# mSniff_v01.net
KiCad netlist of a schematic drawn in EAGLE
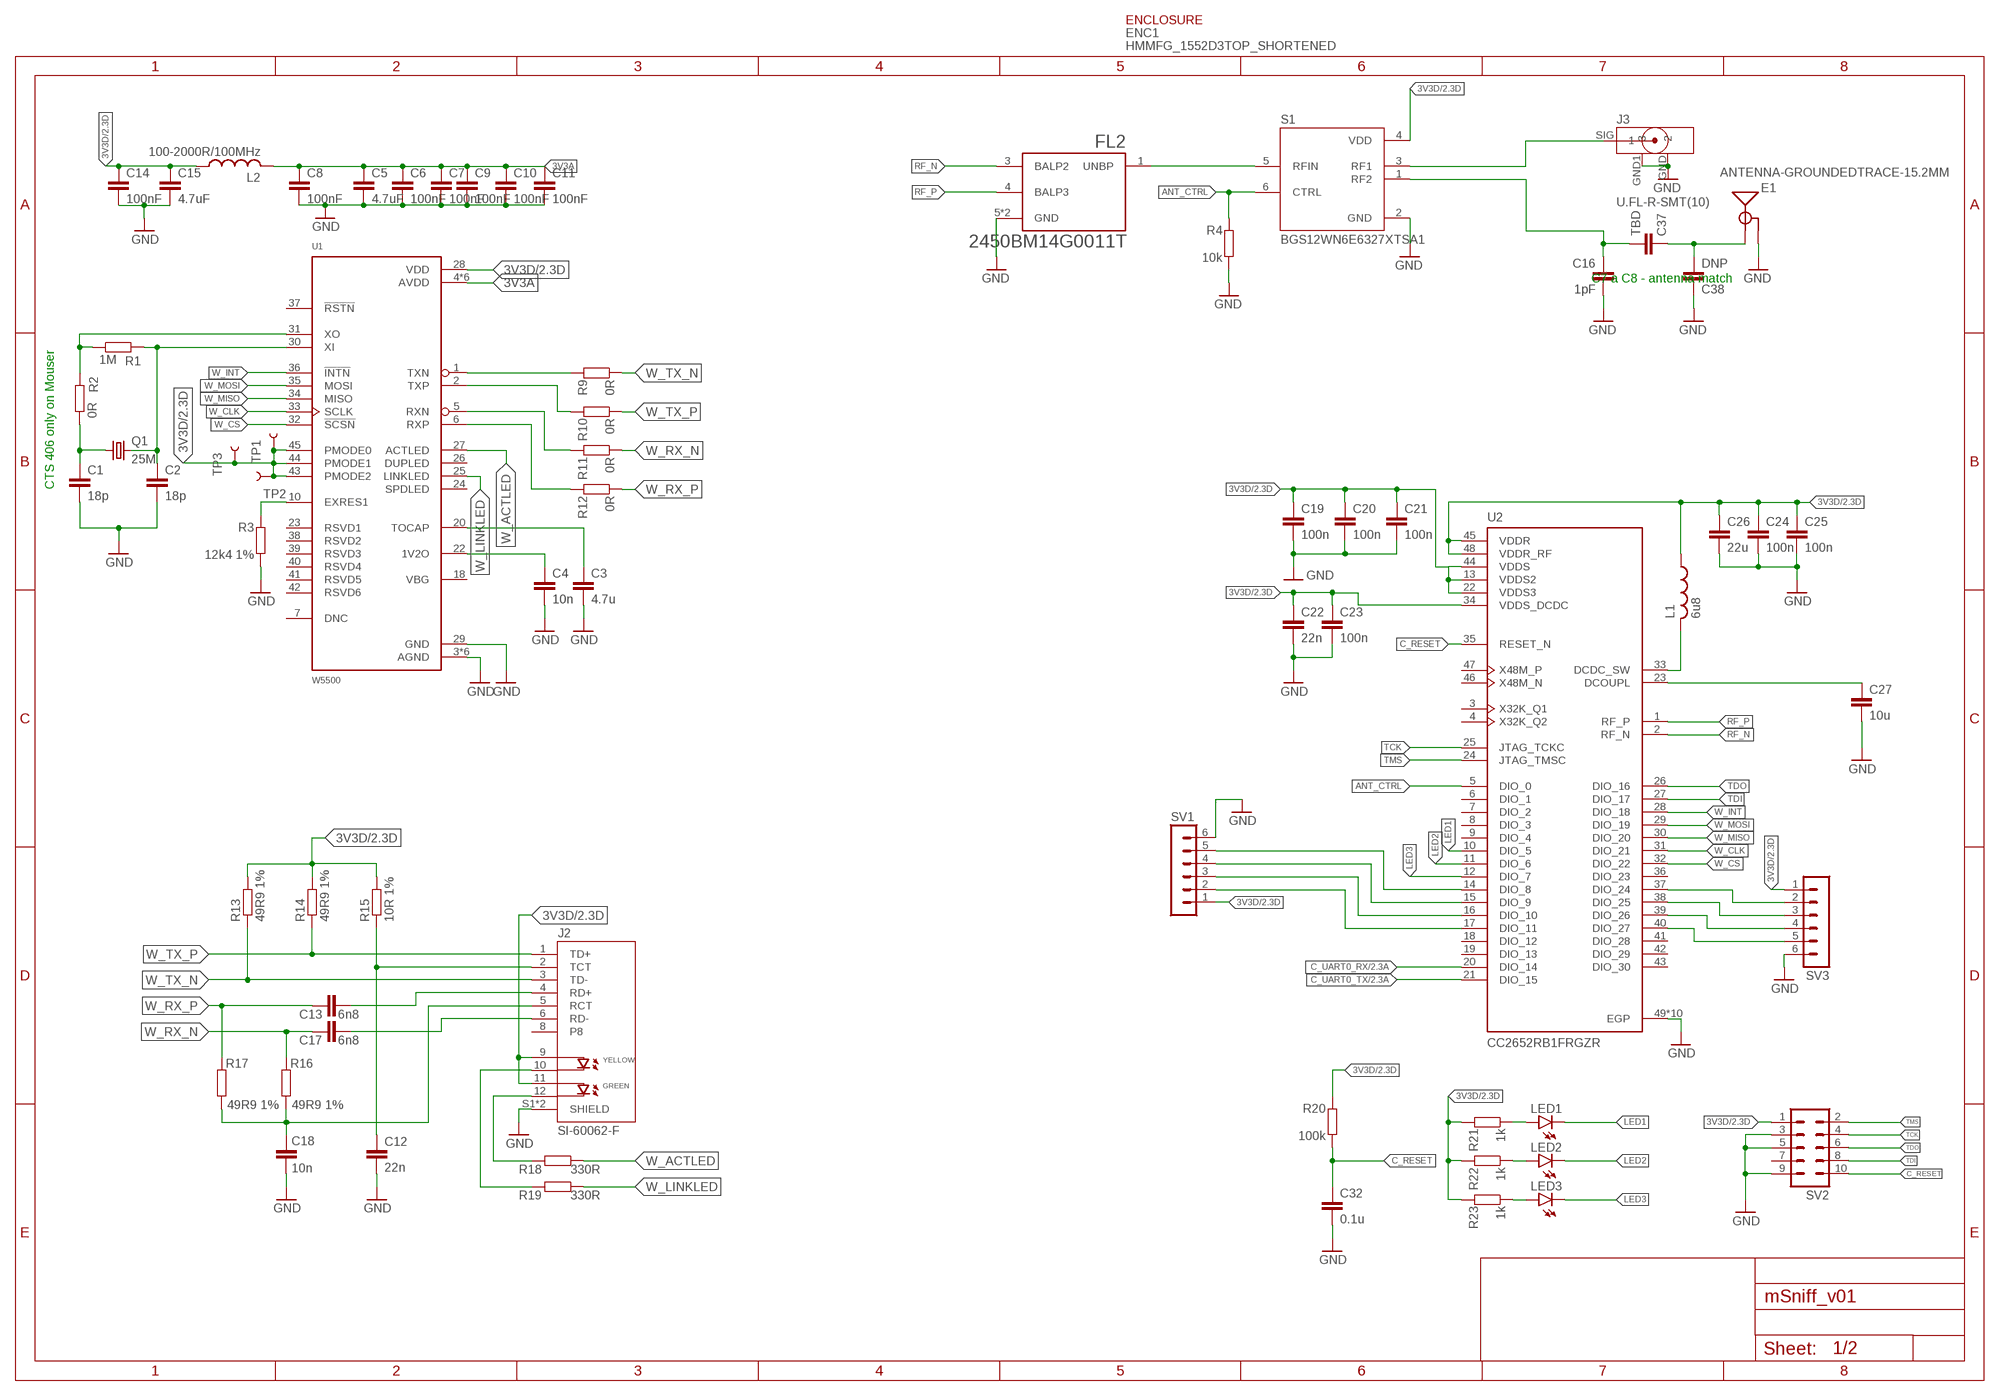
[diagram p0: schematic, sheet 1]
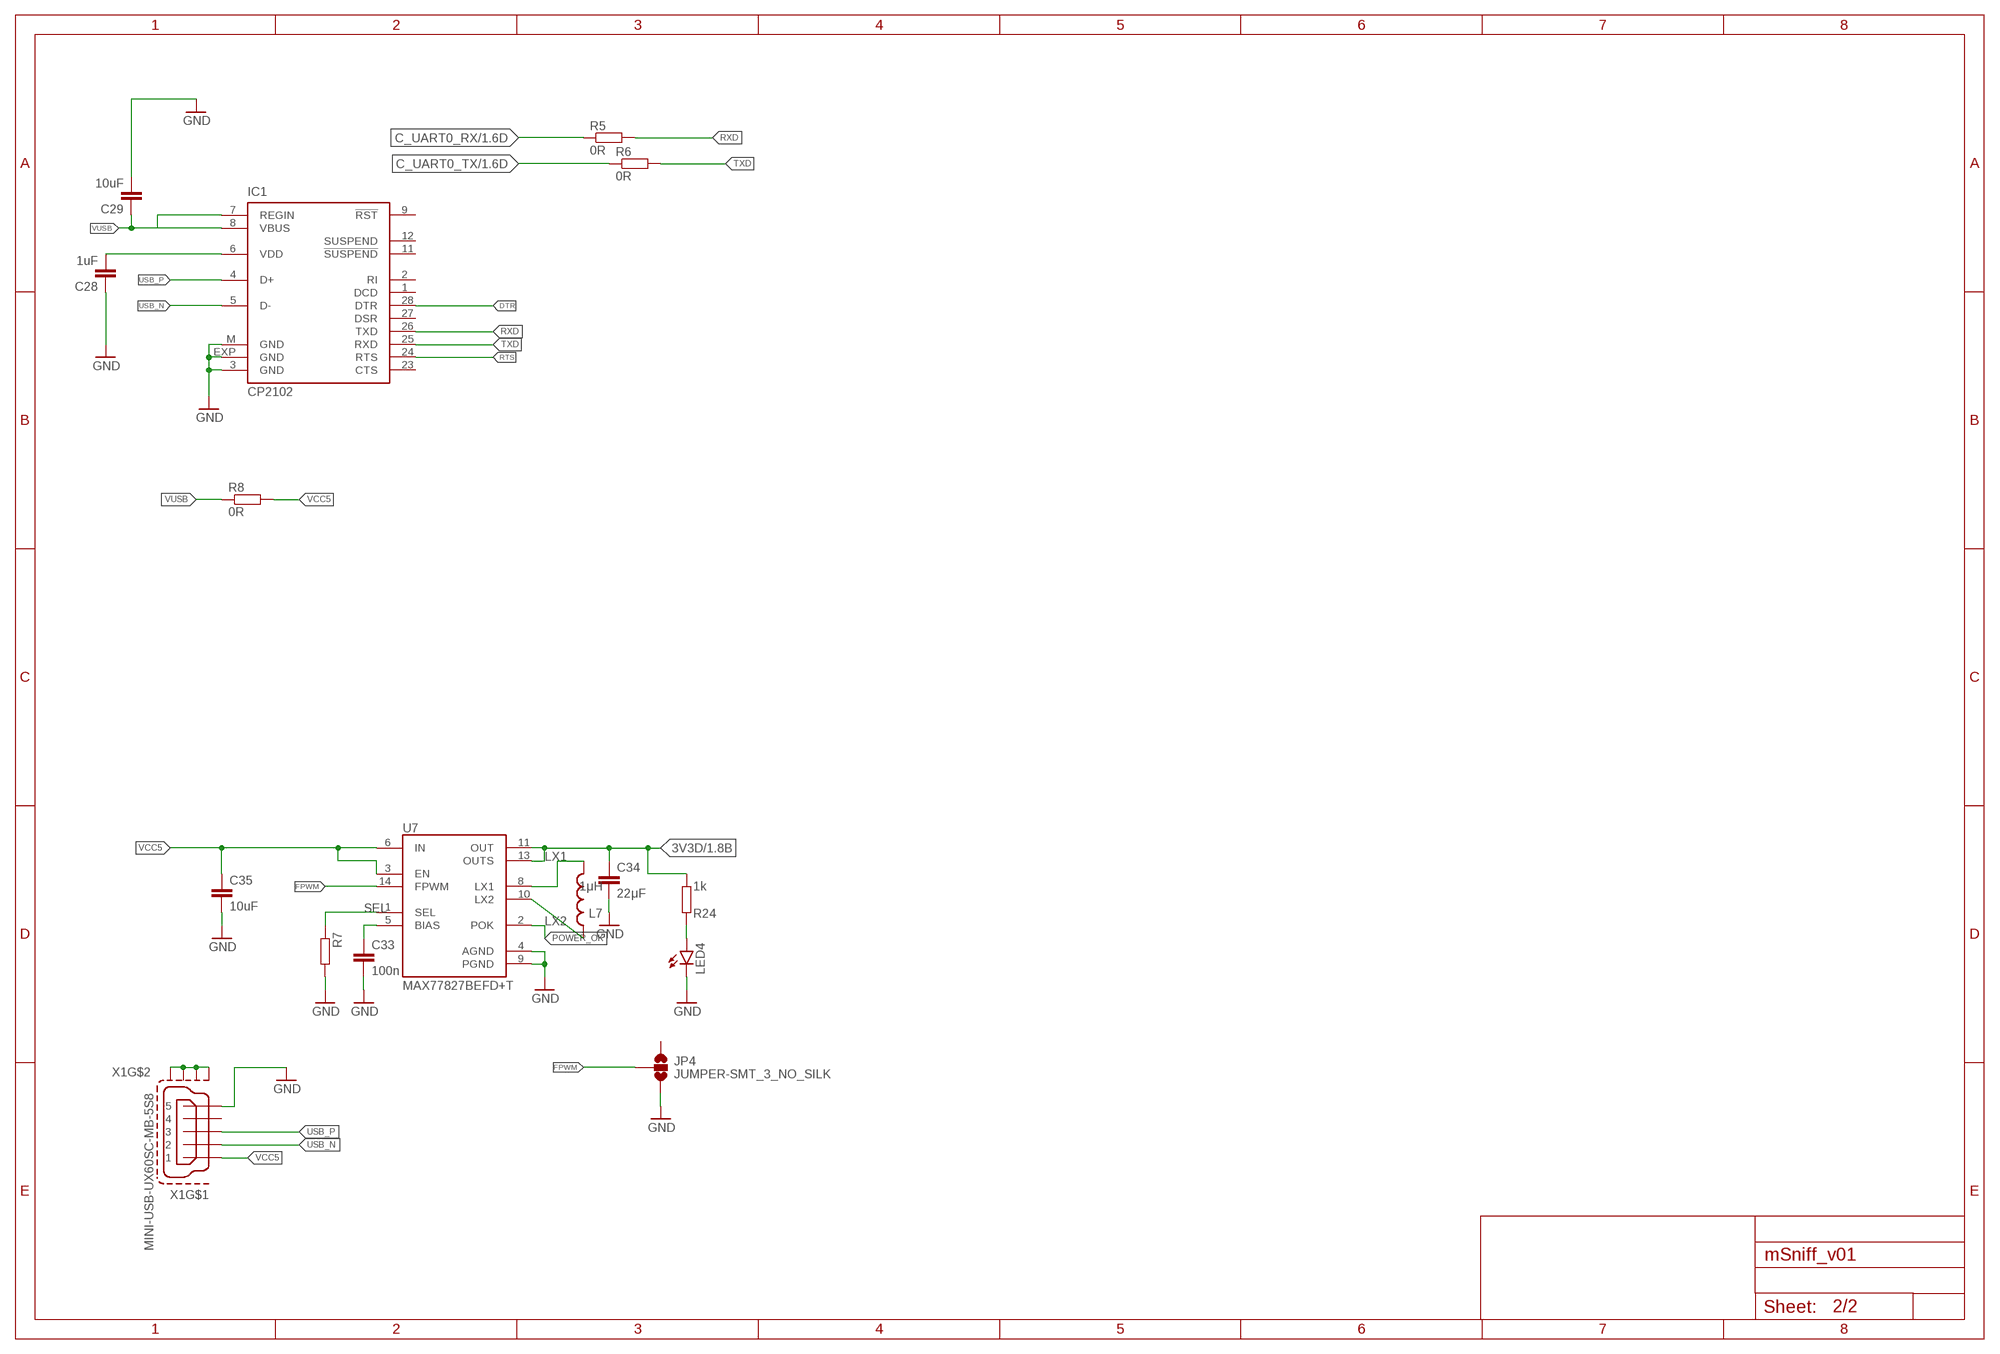
[diagram p1: schematic, sheet 2]

(export (version "E")
  (design (tool "Eeschema 10.0.6"))
  (components
    (comp (ref "C1")
      (value "18p")
      (footprint "eagle-import:0603REC_C")
      (libsource (lib "eagle-import") (part "C_0603REC"))
    )
    (comp (ref "C2")
      (value "18p")
      (footprint "eagle-import:0603REC_C")
      (libsource (lib "eagle-import") (part "C_0603REC"))
    )
    (comp (ref "C3")
      (value "4.7u")
      (footprint "eagle-import:0603REC_C")
      (libsource (lib "eagle-import") (part "C_0603REC"))
    )
    (comp (ref "C4")
      (value "10n")
      (footprint "eagle-import:0603REC_C")
      (libsource (lib "eagle-import") (part "C_0603REC"))
    )
    (comp (ref "C5")
      (value "4.7uF")
      (footprint "eagle-import:0805REC_C")
      (libsource (lib "eagle-import") (part "C_0805REC"))
    )
    (comp (ref "C6")
      (value "100nF")
      (footprint "eagle-import:0603REC_C")
      (libsource (lib "eagle-import") (part "C_0603REC"))
    )
    (comp (ref "C7")
      (value "100nF")
      (footprint "eagle-import:0603REC_C")
      (libsource (lib "eagle-import") (part "C_0603REC"))
    )
    (comp (ref "C8")
      (value "100nF")
      (footprint "eagle-import:0603REC_C")
      (libsource (lib "eagle-import") (part "C_0603REC"))
    )
    (comp (ref "C9")
      (value "100nF")
      (footprint "eagle-import:0603REC_C")
      (libsource (lib "eagle-import") (part "C_0603REC"))
    )
    (comp (ref "C10")
      (value "100nF")
      (footprint "eagle-import:0603REC_C")
      (libsource (lib "eagle-import") (part "C_0603REC"))
    )
    (comp (ref "C11")
      (value "100nF")
      (footprint "eagle-import:0603REC_C")
      (libsource (lib "eagle-import") (part "C_0603REC"))
    )
    (comp (ref "C12")
      (value "22n")
      (footprint "eagle-import:0603REC_C")
      (libsource (lib "eagle-import") (part "C_0603REC"))
    )
    (comp (ref "C13")
      (value "6n8")
      (footprint "eagle-import:0603REC_C")
      (libsource (lib "eagle-import") (part "C_0603REC"))
    )
    (comp (ref "C14")
      (value "100nF")
      (footprint "eagle-import:0603REC_C")
      (libsource (lib "eagle-import") (part "C_0603REC"))
    )
    (comp (ref "C15")
      (value "4.7uF")
      (footprint "eagle-import:0805REC_C")
      (libsource (lib "eagle-import") (part "C_0805REC"))
    )
    (comp (ref "C16")
      (value "1pF")
      (footprint "eagle-import:0402REC_C")
      (libsource (lib "eagle-import") (part "C_0402REC"))
    )
    (comp (ref "C17")
      (value "6n8")
      (footprint "eagle-import:0603REC_C")
      (libsource (lib "eagle-import") (part "C_0603REC"))
    )
    (comp (ref "C18")
      (value "10n")
      (footprint "eagle-import:0603REC_C")
      (libsource (lib "eagle-import") (part "C_0603REC"))
    )
    (comp (ref "C19")
      (value "100n")
      (footprint "eagle-import:0603REC_C")
      (libsource (lib "eagle-import") (part "C_0603REC"))
    )
    (comp (ref "C20")
      (value "100n")
      (footprint "eagle-import:0603REC_C")
      (libsource (lib "eagle-import") (part "C_0603REC"))
    )
    (comp (ref "C21")
      (value "100n")
      (footprint "eagle-import:0603REC_C")
      (libsource (lib "eagle-import") (part "C_0603REC"))
    )
    (comp (ref "C22")
      (value "22n")
      (footprint "eagle-import:0603REC_C")
      (libsource (lib "eagle-import") (part "C_0603REC"))
    )
    (comp (ref "C23")
      (value "100n")
      (footprint "eagle-import:0603REC_C")
      (libsource (lib "eagle-import") (part "C_0603REC"))
    )
    (comp (ref "C24")
      (value "100n")
      (footprint "eagle-import:0603REC_C")
      (libsource (lib "eagle-import") (part "C_0603REC"))
    )
    (comp (ref "C25")
      (value "100n")
      (footprint "eagle-import:0603REC_C")
      (libsource (lib "eagle-import") (part "C_0603REC"))
    )
    (comp (ref "C26")
      (value "22u")
      (footprint "eagle-import:0603REC_C")
      (libsource (lib "eagle-import") (part "C_0603REC"))
    )
    (comp (ref "C27")
      (value "10u")
      (footprint "eagle-import:0603REC_C")
      (libsource (lib "eagle-import") (part "C_0603REC"))
    )
    (comp (ref "C32")
      (value "0.1u")
      (footprint "eagle-import:0603REC_C")
      (libsource (lib "eagle-import") (part "C_0603REC"))
    )
    (comp (ref "C37")
      (value "TBD")
      (footprint "eagle-import:0402REC_C")
      (libsource (lib "eagle-import") (part "C_0402REC"))
    )
    (comp (ref "C38")
      (value "DNP")
      (footprint "eagle-import:0402REC_C")
      (libsource (lib "eagle-import") (part "C_0402REC"))
    )
    (comp (ref "E1")
      (value "ANTENNA-GROUNDEDTRACE-15.2MM")
      (footprint "eagle-import:TRACE_ANTENNA_2.4GHZ_15.2MM")
      (libsource (lib "eagle-import") (part "ANTENNA-GROUNDEDTRACE-15.2MM"))
    )
    (comp (ref "ENC1")
      (value "HMMFG_1552D3TOP_SHORTENED")
      (footprint "eagle-import:1552D3_TOP_SHORT")
      (libsource (lib "eagle-import") (part "HMMFG_1552D3TOP_SHORTENED"))
    )
    (comp (ref "FL2")
      (value "2450BM14G0011T")
      (footprint "eagle-import:BALUN_2450BM14G0011T")
      (fields (field (name "MF") "Johanson Technology"))
      (libsource (lib "eagle-import") (part "2450BM14G0011T"))
    )
    (comp (ref "J2")
      (value "SI-60062-F")
      (footprint "eagle-import:BEL_SI-60062-F")
      (fields (field (name "MF") "Bel Magnetic Solutions"))
      (libsource (lib "eagle-import") (part "SI-60062-F"))
    )
    (comp (ref "J3")
      (value "U.FL-R-SMT(10)")
      (footprint "eagle-import:U.FL-R-SMT(10)")
      (fields
        (field (name "DIGIKEY_PART_NUMBER") "H9161CT-ND")
        (field (name "MANUFACTURER") "Hirose Electric Co Ltd")
        (field (name "CREATED_BY") "PCBLayout.com")
      )
      (libsource (lib "eagle-import") (part "U.FL-R-SMT(10)"))
    )
    (comp (ref "L1")
      (value "6u8")
      (footprint "eagle-import:0805REC_L")
      (libsource (lib "eagle-import") (part "L_0805REC"))
    )
    (comp (ref "L2")
      (value "100-2000R/100MHz")
      (footprint "eagle-import:0603REC_L")
      (libsource (lib "eagle-import") (part "L_0603REC"))
    )
    (comp (ref "LED1")
      (value "LEDCHIPLED_0603")
      (footprint "eagle-import:CHIPLED_0603")
      (libsource (lib "eagle-import") (part "LEDCHIPLED_0603"))
    )
    (comp (ref "LED2")
      (value "LEDCHIPLED_0603")
      (footprint "eagle-import:CHIPLED_0603")
      (libsource (lib "eagle-import") (part "LEDCHIPLED_0603"))
    )
    (comp (ref "LED3")
      (value "LEDCHIPLED_0603")
      (footprint "eagle-import:CHIPLED_0603")
      (libsource (lib "eagle-import") (part "LEDCHIPLED_0603"))
    )
    (comp (ref "Q1")
      (value "25M")
      (footprint "eagle-import:CTS406")
      (libsource (lib "eagle-import") (part "CRYSTALCTS406"))
    )
    (comp (ref "R1")
      (value "1M")
      (footprint "eagle-import:0603REC_R")
      (libsource (lib "eagle-import") (part "R_0603REC"))
    )
    (comp (ref "R2")
      (value "0R")
      (footprint "eagle-import:0603REC_R")
      (libsource (lib "eagle-import") (part "R_0603REC"))
    )
    (comp (ref "R3")
      (value "12k4 1%")
      (footprint "eagle-import:0603REC_R")
      (libsource (lib "eagle-import") (part "R_0603REC"))
    )
    (comp (ref "R4")
      (value "10k")
      (footprint "eagle-import:0603REC_R")
      (libsource (lib "eagle-import") (part "R_0603REC"))
    )
    (comp (ref "R9")
      (value "0R")
      (footprint "eagle-import:0603REC_R")
      (libsource (lib "eagle-import") (part "R_0603REC"))
    )
    (comp (ref "R10")
      (value "0R")
      (footprint "eagle-import:0603REC_R")
      (libsource (lib "eagle-import") (part "R_0603REC"))
    )
    (comp (ref "R11")
      (value "0R")
      (footprint "eagle-import:0603REC_R")
      (libsource (lib "eagle-import") (part "R_0603REC"))
    )
    (comp (ref "R12")
      (value "0R")
      (footprint "eagle-import:0603REC_R")
      (libsource (lib "eagle-import") (part "R_0603REC"))
    )
    (comp (ref "R13")
      (value "49R9 1%")
      (footprint "eagle-import:0603REC_R")
      (libsource (lib "eagle-import") (part "R_0603REC"))
    )
    (comp (ref "R14")
      (value "49R9 1%")
      (footprint "eagle-import:0603REC_R")
      (libsource (lib "eagle-import") (part "R_0603REC"))
    )
    (comp (ref "R15")
      (value "10R 1%")
      (footprint "eagle-import:0603REC_R")
      (libsource (lib "eagle-import") (part "R_0603REC"))
    )
    (comp (ref "R16")
      (value "49R9 1%")
      (footprint "eagle-import:0603REC_R")
      (libsource (lib "eagle-import") (part "R_0603REC"))
    )
    (comp (ref "R17")
      (value "49R9 1%")
      (footprint "eagle-import:0603REC_R")
      (libsource (lib "eagle-import") (part "R_0603REC"))
    )
    (comp (ref "R18")
      (value "330R")
      (footprint "eagle-import:0603REC_R")
      (libsource (lib "eagle-import") (part "R_0603REC"))
    )
    (comp (ref "R19")
      (value "330R")
      (footprint "eagle-import:0603REC_R")
      (libsource (lib "eagle-import") (part "R_0603REC"))
    )
    (comp (ref "R20")
      (value "100k")
      (footprint "eagle-import:0603REC_R")
      (libsource (lib "eagle-import") (part "R_0603REC"))
    )
    (comp (ref "R21")
      (value "1k")
      (footprint "eagle-import:0603REC_R")
      (libsource (lib "eagle-import") (part "R_0603REC"))
    )
    (comp (ref "R22")
      (value "1k")
      (footprint "eagle-import:0603REC_R")
      (libsource (lib "eagle-import") (part "R_0603REC"))
    )
    (comp (ref "R23")
      (value "1k")
      (footprint "eagle-import:0603REC_R")
      (libsource (lib "eagle-import") (part "R_0603REC"))
    )
    (comp (ref "S1")
      (value "BGS12WN6E6327XTSA1")
      (footprint "eagle-import:SW_BGS12WN6E6327XTSA1")
      (fields (field (name "MF") "Infineon Technologies"))
      (libsource (lib "eagle-import") (part "BGS12WN6E6327XTSA1"))
    )
    (comp (ref "SV1")
      (value "MA06-1")
      (footprint "eagle-import:MA06-1")
      (libsource (lib "eagle-import") (part "MA06-1"))
    )
    (comp (ref "SV2")
      (value "MA05-2SMD127")
      (footprint "eagle-import:MA05-2-SMD127-GPEC214")
      (libsource (lib "eagle-import") (part "MA05-2SMD127"))
    )
    (comp (ref "SV3")
      (value "MA06-1")
      (footprint "eagle-import:MA06-1")
      (libsource (lib "eagle-import") (part "MA06-1"))
    )
    (comp (ref "TP1")
      (value "TEST-POINT3")
      (footprint "eagle-import:PAD.03X.03")
      (libsource (lib "eagle-import") (part "TEST-POINT3"))
    )
    (comp (ref "TP2")
      (value "TEST-POINT3")
      (footprint "eagle-import:PAD.03X.03")
      (libsource (lib "eagle-import") (part "TEST-POINT3"))
    )
    (comp (ref "TP3")
      (value "TEST-POINT3")
      (footprint "eagle-import:PAD.03X.03")
      (libsource (lib "eagle-import") (part "TEST-POINT3"))
    )
    (comp (ref "U1")
      (value "W5500")
      (footprint "eagle-import:QFP50P900X900X160-48N")
      (fields (field (name "MF") "WIZnet"))
      (libsource (lib "eagle-import") (part "W5500"))
    )
    (comp (ref "U2")
      (value "CC2652RB1FRGZR")
      (footprint "eagle-import:QFN50P700X700X100-49N")
      (fields (field (name "MF") "Texas Instruments"))
      (libsource (lib "eagle-import") (part "CC2652RB1FRGZR"))
    )
    (comp (ref "C28")
      (value "1uF")
      (footprint "eagle-import:0603REC_C")
      (libsource (lib "eagle-import") (part "C_0603REC"))
    )
    (comp (ref "C29")
      (value "10uF")
      (footprint "eagle-import:0603REC_C")
      (libsource (lib "eagle-import") (part "C_0603REC"))
    )
    (comp (ref "C33")
      (value "100n")
      (footprint "eagle-import:0603REC_C")
      (libsource (lib "eagle-import") (part "C_0603REC"))
    )
    (comp (ref "C34")
      (value "22μF")
      (footprint "eagle-import:0603REC_C")
      (libsource (lib "eagle-import") (part "C_0603REC"))
    )
    (comp (ref "C35")
      (value "10uF")
      (footprint "eagle-import:0603REC_C")
      (libsource (lib "eagle-import") (part "C_0603REC"))
    )
    (comp (ref "IC1")
      (value "CP2102")
      (footprint "eagle-import:MLP28")
      (fields (field (name "MF") "FARNELL") (field (name "MPN") "CP2102-GM"))
      (libsource (lib "eagle-import") (part "CP2102"))
    )
    (comp (ref "JP4")
      (value "JUMPER-SMT_3_NO_SILK")
      (footprint "eagle-import:SMT-JUMPER_3_NO_SILK")
      (libsource (lib "eagle-import") (part "JUMPER-SMT_3_NO_SILK"))
    )
    (comp (ref "L7")
      (value "1μH")
      (footprint "eagle-import:1008REC_L")
      (libsource (lib "eagle-import") (part "L_1008REC"))
    )
    (comp (ref "LED4")
      (value "LEDCHIPLED_0603")
      (footprint "eagle-import:CHIPLED_0603")
      (libsource (lib "eagle-import") (part "LEDCHIPLED_0603"))
    )
    (comp (ref "R5")
      (value "0R")
      (footprint "eagle-import:0603REC_R")
      (libsource (lib "eagle-import") (part "R_0603REC"))
    )
    (comp (ref "R6")
      (value "0R")
      (footprint "eagle-import:0603REC_R")
      (libsource (lib "eagle-import") (part "R_0603REC"))
    )
    (comp (ref "R7")
      (value "R_0603REC")
      (footprint "eagle-import:0603REC_R")
      (libsource (lib "eagle-import") (part "R_0603REC"))
    )
    (comp (ref "R8")
      (value "0R")
      (footprint "eagle-import:0603REC_R")
      (libsource (lib "eagle-import") (part "R_0603REC"))
    )
    (comp (ref "R24")
      (value "1k")
      (footprint "eagle-import:0603REC_R")
      (libsource (lib "eagle-import") (part "R_0603REC"))
    )
    (comp (ref "U7")
      (value "MAX77827BEFD+T")
      (footprint "eagle-import:CONV_MAX77827BEFD+T")
      (fields (field (name "MF") "Analog Devices"))
      (libsource (lib "eagle-import") (part "MAX77827BEFD+T"))
    )
    (comp (ref "X1")
      (value "MINI-USB-UX60SC-MB-5S8")
      (footprint "eagle-import:HIROSE_UX60SC-MB-5S8")
      (libsource (lib "eagle-import") (part "MINI-USB-UX60SC-MB-5S8"))
    )
  )
  (nets
    (net (code "1") (name "3V3A") (class "Default")
      (node (ref "C10") (pin "1") (pinfunction "1_1") (pintype "passive"))
      (node (ref "C11") (pin "1") (pinfunction "1_1") (pintype "passive"))
      (node (ref "C5") (pin "1") (pinfunction "1_1") (pintype "passive"))
      (node (ref "C6") (pin "1") (pinfunction "1_1") (pintype "passive"))
      (node (ref "C7") (pin "1") (pinfunction "1_1") (pintype "passive"))
      (node (ref "C8") (pin "1") (pinfunction "1_1") (pintype "passive"))
      (node (ref "C9") (pin "1") (pinfunction "1_1") (pintype "passive"))
      (node (ref "L2") (pin "2") (pinfunction "2_2") (pintype "passive"))
      (node (ref "U1") (pin "11") (pinfunction "AVDD_11") (pintype "power_in"))
      (node (ref "U1") (pin "15") (pinfunction "AVDD_15") (pintype "power_in"))
      (node (ref "U1") (pin "17") (pinfunction "AVDD_17") (pintype "power_in"))
      (node (ref "U1") (pin "21") (pinfunction "AVDD_21") (pintype "power_in"))
      (node (ref "U1") (pin "4") (pinfunction "AVDD_4") (pintype "power_in"))
      (node (ref "U1") (pin "8") (pinfunction "AVDD_8") (pintype "power_in"))
    )
    (net (code "2") (name "3V3D") (class "Default")
      (node (ref "C14") (pin "1") (pinfunction "1_1") (pintype "passive"))
      (node (ref "C15") (pin "1") (pinfunction "1_1") (pintype "passive"))
      (node (ref "C19") (pin "1") (pinfunction "1_1") (pintype "passive"))
      (node (ref "C20") (pin "1") (pinfunction "1_1") (pintype "passive"))
      (node (ref "C21") (pin "1") (pinfunction "1_1") (pintype "passive"))
      (node (ref "C22") (pin "1") (pinfunction "1_1") (pintype "passive"))
      (node (ref "C23") (pin "1") (pinfunction "1_1") (pintype "passive"))
      (node (ref "C24") (pin "1") (pinfunction "1_1") (pintype "passive"))
      (node (ref "C25") (pin "1") (pinfunction "1_1") (pintype "passive"))
      (node (ref "C26") (pin "1") (pinfunction "1_1") (pintype "passive"))
      (node (ref "C34") (pin "1") (pinfunction "1_1") (pintype "passive"))
      (node (ref "J2") (pin "11") (pinfunction "GA_11") (pintype "passive"))
      (node (ref "J2") (pin "9") (pinfunction "YA_9") (pintype "passive"))
      (node (ref "L1") (pin "1") (pinfunction "1_1") (pintype "passive"))
      (node (ref "L2") (pin "1") (pinfunction "1_1") (pintype "passive"))
      (node (ref "R13") (pin "2") (pinfunction "2_2") (pintype "passive"))
      (node (ref "R14") (pin "2") (pinfunction "2_2") (pintype "passive"))
      (node (ref "R15") (pin "2") (pinfunction "2_2") (pintype "passive"))
      (node (ref "R20") (pin "2") (pinfunction "2_2") (pintype "passive"))
      (node (ref "R21") (pin "2") (pinfunction "2_2") (pintype "passive"))
      (node (ref "R22") (pin "2") (pinfunction "2_2") (pintype "passive"))
      (node (ref "R23") (pin "2") (pinfunction "2_2") (pintype "passive"))
      (node (ref "R24") (pin "1") (pinfunction "1_1") (pintype "passive"))
      (node (ref "S1") (pin "4") (pinfunction "VDD_4") (pintype "power_in"))
      (node (ref "SV1") (pin "1") (pinfunction "1_1") (pintype "passive"))
      (node (ref "SV2") (pin "1") (pinfunction "1_1") (pintype "passive"))
      (node (ref "SV3") (pin "1") (pinfunction "1_1") (pintype "passive"))
      (node (ref "TP1") (pin "P$1") (pinfunction "1_P$1") (pintype "bidirectional"))
      (node (ref "TP2") (pin "P$1") (pinfunction "1_P$1") (pintype "bidirectional"))
      (node (ref "TP3") (pin "P$1") (pinfunction "1_P$1") (pintype "bidirectional"))
      (node (ref "U1") (pin "28") (pinfunction "VDD_28") (pintype "power_in"))
      (node (ref "U1") (pin "43") (pinfunction "PMODE2_43") (pintype "input"))
      (node (ref "U1") (pin "44") (pinfunction "PMODE1_44") (pintype "input"))
      (node (ref "U1") (pin "45") (pinfunction "PMODE0_45") (pintype "input"))
      (node (ref "U2") (pin "13") (pinfunction "VDDS2_13") (pintype "power_in"))
      (node (ref "U2") (pin "22") (pinfunction "VDDS3_22") (pintype "power_in"))
      (node (ref "U2") (pin "34") (pinfunction "VDDS_DCDC_34") (pintype "power_in"))
      (node (ref "U2") (pin "44") (pinfunction "VDDS_44") (pintype "power_in"))
      (node (ref "U2") (pin "45") (pinfunction "VDDR_45") (pintype "power_in"))
      (node (ref "U2") (pin "48") (pinfunction "VDDR_RF_48") (pintype "power_in"))
      (node (ref "U7") (pin "11") (pinfunction "OUT_11") (pintype "output"))
      (node (ref "U7") (pin "13") (pinfunction "OUTS_13") (pintype "input"))
    )
    (net (code "3") (name "ANT_CTRL") (class "Default")
      (node (ref "R4") (pin "2") (pinfunction "2_2") (pintype "passive"))
      (node (ref "S1") (pin "6") (pinfunction "CTRL_6") (pintype "input"))
      (node (ref "U2") (pin "5") (pinfunction "DIO_0_5") (pintype "bidirectional"))
    )
    (net (code "4") (name "C_RESET") (class "Default")
      (node (ref "C32") (pin "1") (pinfunction "1_1") (pintype "passive"))
      (node (ref "R20") (pin "1") (pinfunction "1_1") (pintype "passive"))
      (node (ref "SV2") (pin "10") (pinfunction "10_10") (pintype "passive"))
      (node (ref "U2") (pin "35") (pinfunction "RESET_N_35") (pintype "input"))
    )
    (net (code "5") (name "C_UART0_RX") (class "Default")
      (node (ref "R5") (pin "1") (pinfunction "1_1") (pintype "passive"))
      (node (ref "U2") (pin "20") (pinfunction "DIO_14_20") (pintype "bidirectional"))
    )
    (net (code "6") (name "C_UART0_TX") (class "Default")
      (node (ref "R6") (pin "1") (pinfunction "1_1") (pintype "passive"))
      (node (ref "U2") (pin "21") (pinfunction "DIO_15_21") (pintype "bidirectional"))
    )
    (net (code "7") (name "DTR") (class "Default")
      (node (ref "IC1") (pin "28") (pinfunction "DTR_28") (pintype "output"))
    )
    (net (code "8") (name "FPWM") (class "Default")
      (node (ref "JP4") (pin "2") (pinfunction "2_2") (pintype "passive"))
      (node (ref "U7") (pin "14") (pinfunction "FPWM_14") (pintype "input"))
    )
    (net (code "9") (name "GND") (class "Default")
      (node (ref "C1") (pin "2") (pinfunction "2_2") (pintype "passive"))
      (node (ref "C10") (pin "2") (pinfunction "2_2") (pintype "passive"))
      (node (ref "C11") (pin "2") (pinfunction "2_2") (pintype "passive"))
      (node (ref "C12") (pin "2") (pinfunction "2_2") (pintype "passive"))
      (node (ref "C14") (pin "2") (pinfunction "2_2") (pintype "passive"))
      (node (ref "C15") (pin "2") (pinfunction "2_2") (pintype "passive"))
      (node (ref "C16") (pin "2") (pinfunction "2_2") (pintype "passive"))
      (node (ref "C18") (pin "1") (pinfunction "1_1") (pintype "passive"))
      (node (ref "C19") (pin "2") (pinfunction "2_2") (pintype "passive"))
      (node (ref "C2") (pin "2") (pinfunction "2_2") (pintype "passive"))
      (node (ref "C20") (pin "2") (pinfunction "2_2") (pintype "passive"))
      (node (ref "C21") (pin "2") (pinfunction "2_2") (pintype "passive"))
      (node (ref "C22") (pin "2") (pinfunction "2_2") (pintype "passive"))
      (node (ref "C23") (pin "2") (pinfunction "2_2") (pintype "passive"))
      (node (ref "C24") (pin "2") (pinfunction "2_2") (pintype "passive"))
      (node (ref "C25") (pin "2") (pinfunction "2_2") (pintype "passive"))
      (node (ref "C26") (pin "2") (pinfunction "2_2") (pintype "passive"))
      (node (ref "C27") (pin "2") (pinfunction "2_2") (pintype "passive"))
      (node (ref "C28") (pin "1") (pinfunction "1_1") (pintype "passive"))
      (node (ref "C29") (pin "2") (pinfunction "2_2") (pintype "passive"))
      (node (ref "C3") (pin "2") (pinfunction "2_2") (pintype "passive"))
      (node (ref "C32") (pin "2") (pinfunction "2_2") (pintype "passive"))
      (node (ref "C33") (pin "2") (pinfunction "2_2") (pintype "passive"))
      (node (ref "C34") (pin "2") (pinfunction "2_2") (pintype "passive"))
      (node (ref "C35") (pin "2") (pinfunction "2_2") (pintype "passive"))
      (node (ref "C38") (pin "1") (pinfunction "1_1") (pintype "passive"))
      (node (ref "C4") (pin "2") (pinfunction "2_2") (pintype "passive"))
      (node (ref "C5") (pin "2") (pinfunction "2_2") (pintype "passive"))
      (node (ref "C6") (pin "2") (pinfunction "2_2") (pintype "passive"))
      (node (ref "C7") (pin "2") (pinfunction "2_2") (pintype "passive"))
      (node (ref "C8") (pin "2") (pinfunction "2_2") (pintype "passive"))
      (node (ref "C9") (pin "2") (pinfunction "2_2") (pintype "passive"))
      (node (ref "E1") (pin "GND") (pinfunction "GND_GND") (pintype "bidirectional"))
      (node (ref "FL2") (pin "5") (pinfunction "GND_5") (pintype "power_in"))
      (node (ref "FL2") (pin "6") (pinfunction "GND_6") (pintype "power_in"))
      (node (ref "IC1") (pin "3") (pinfunction "GND_3") (pintype "power_in"))
      (node (ref "IC1") (pin "EXP") (pinfunction "GND_EXP") (pintype "power_in"))
      (node (ref "IC1") (pin "M") (pinfunction "GND_M") (pintype "power_in"))
      (node (ref "J2") (pin "S1") (pinfunction "SHIELD_S1") (pintype "passive"))
      (node (ref "J2") (pin "S2") (pinfunction "SHIELD_S2") (pintype "passive"))
      (node (ref "J3") (pin "GND") (pinfunction "2_GND") (pintype "passive"))
      (node (ref "J3") (pin "GND1") (pinfunction "3_GND1") (pintype "passive"))
      (node (ref "JP4") (pin "3") (pinfunction "3_3") (pintype "passive"))
      (node (ref "LED4") (pin "C") (pinfunction "C_C") (pintype "passive"))
      (node (ref "R3") (pin "1") (pinfunction "1_1") (pintype "passive"))
      (node (ref "R4") (pin "1") (pinfunction "1_1") (pintype "passive"))
      (node (ref "R7") (pin "2") (pinfunction "2_2") (pintype "passive"))
      (node (ref "S1") (pin "2") (pinfunction "GND_2") (pintype "power_in"))
      (node (ref "SV1") (pin "6") (pinfunction "6_6") (pintype "passive"))
      (node (ref "SV2") (pin "3") (pinfunction "3_3") (pintype "passive"))
      (node (ref "SV2") (pin "5") (pinfunction "5_5") (pintype "passive"))
      (node (ref "SV2") (pin "9") (pinfunction "9_9") (pintype "passive"))
      (node (ref "SV3") (pin "6") (pinfunction "6_6") (pintype "passive"))
      (node (ref "U1") (pin "14") (pinfunction "AGND_14") (pintype "power_in"))
      (node (ref "U1") (pin "16") (pinfunction "AGND_16") (pintype "power_in"))
      (node (ref "U1") (pin "19") (pinfunction "AGND_19") (pintype "power_in"))
      (node (ref "U1") (pin "29") (pinfunction "GND_29") (pintype "passive"))
      (node (ref "U1") (pin "3") (pinfunction "AGND_3") (pintype "power_in"))
      (node (ref "U1") (pin "48") (pinfunction "AGND_48") (pintype "power_in"))
      (node (ref "U1") (pin "9") (pinfunction "AGND_9") (pintype "power_in"))
      (node (ref "U2") (pin "49") (pinfunction "EGP_49") (pintype "power_in"))
      (node (ref "U2") (pin "50") (pinfunction "EGP_50") (pintype "power_in"))
      (node (ref "U2") (pin "51") (pinfunction "EGP_51") (pintype "power_in"))
      (node (ref "U2") (pin "52") (pinfunction "EGP_52") (pintype "power_in"))
      (node (ref "U2") (pin "53") (pinfunction "EGP_53") (pintype "power_in"))
      (node (ref "U2") (pin "54") (pinfunction "EGP_54") (pintype "power_in"))
      (node (ref "U2") (pin "55") (pinfunction "EGP_55") (pintype "power_in"))
      (node (ref "U2") (pin "56") (pinfunction "EGP_56") (pintype "power_in"))
      (node (ref "U2") (pin "57") (pinfunction "EGP_57") (pintype "power_in"))
      (node (ref "U2") (pin "58") (pinfunction "EGP_58") (pintype "power_in"))
      (node (ref "U7") (pin "4") (pinfunction "AGND_4") (pintype "power_in"))
      (node (ref "U7") (pin "9") (pinfunction "PGND_9") (pintype "power_in"))
      (node (ref "X1") (pin "5") (pinfunction "5_5") (pintype "input"))
    )
    (net (code "10") (name "LED1") (class "Default")
      (node (ref "LED1") (pin "C") (pinfunction "C_C") (pintype "passive"))
      (node (ref "U2") (pin "10") (pinfunction "DIO_5_10") (pintype "bidirectional"))
    )
    (net (code "11") (name "LED2") (class "Default")
      (node (ref "LED2") (pin "C") (pinfunction "C_C") (pintype "passive"))
      (node (ref "U2") (pin "11") (pinfunction "DIO_6_11") (pintype "bidirectional"))
    )
    (net (code "12") (name "LED3") (class "Default")
      (node (ref "LED3") (pin "C") (pinfunction "C_C") (pintype "passive"))
      (node (ref "U2") (pin "12") (pinfunction "DIO_7_12") (pintype "bidirectional"))
    )
    (net (code "13") (name "LX1") (class "Default")
      (node (ref "L7") (pin "2") (pinfunction "2_2") (pintype "passive"))
      (node (ref "U7") (pin "8") (pinfunction "LX1_8") (pintype "passive"))
    )
    (net (code "14") (name "LX2") (class "Default")
      (node (ref "L7") (pin "1") (pinfunction "1_1") (pintype "passive"))
      (node (ref "U7") (pin "10") (pinfunction "LX2_10") (pintype "passive"))
    )
    (net (code "15") (name "Net-(C1-Pad1)") (class "Default")
      (node (ref "C1") (pin "1") (pinfunction "1_1") (pintype "passive"))
      (node (ref "Q1") (pin "1") (pinfunction "1_1") (pintype "passive"))
      (node (ref "R2") (pin "1") (pinfunction "1_1") (pintype "passive"))
    )
    (net (code "16") (name "Net-(E1-SIGNAL)") (class "Default")
      (node (ref "C37") (pin "1") (pinfunction "1_1") (pintype "passive"))
      (node (ref "C38") (pin "2") (pinfunction "2_2") (pintype "passive"))
      (node (ref "E1") (pin "ANT") (pinfunction "SIGNAL_ANT") (pintype "bidirectional"))
    )
    (net (code "17") (name "Net-(FL2-UNBP)") (class "Default")
      (node (ref "FL2") (pin "1") (pinfunction "UNBP_1") (pintype "passive"))
      (node (ref "S1") (pin "5") (pinfunction "RFIN_5") (pintype "input"))
    )
    (net (code "18") (name "Net-(IC1-VDD)") (class "Default")
      (node (ref "C28") (pin "2") (pinfunction "2_2") (pintype "passive"))
      (node (ref "IC1") (pin "6") (pinfunction "VDD_6") (pintype "power_in"))
    )
    (net (code "19") (name "Net-(J2-GK)") (class "Default")
      (node (ref "J2") (pin "12") (pinfunction "GK_12") (pintype "passive"))
      (node (ref "R18") (pin "2") (pinfunction "2_2") (pintype "passive"))
    )
    (net (code "20") (name "Net-(J2-RCT)") (class "Default")
      (node (ref "C18") (pin "2") (pinfunction "2_2") (pintype "passive"))
      (node (ref "J2") (pin "5") (pinfunction "RCT_5") (pintype "passive"))
      (node (ref "R16") (pin "1") (pinfunction "1_1") (pintype "passive"))
      (node (ref "R17") (pin "1") (pinfunction "1_1") (pintype "passive"))
    )
    (net (code "21") (name "Net-(J2-RD+)") (class "Default")
      (node (ref "C13") (pin "2") (pinfunction "2_2") (pintype "passive"))
      (node (ref "J2") (pin "4") (pinfunction "RD+_4") (pintype "passive"))
    )
    (net (code "22") (name "Net-(J2-RD-)") (class "Default")
      (node (ref "C17") (pin "2") (pinfunction "2_2") (pintype "passive"))
      (node (ref "J2") (pin "6") (pinfunction "RD-_6") (pintype "passive"))
    )
    (net (code "23") (name "Net-(J2-TCT)") (class "Default")
      (node (ref "C12") (pin "1") (pinfunction "1_1") (pintype "passive"))
      (node (ref "J2") (pin "2") (pinfunction "TCT_2") (pintype "passive"))
      (node (ref "R15") (pin "1") (pinfunction "1_1") (pintype "passive"))
    )
    (net (code "24") (name "Net-(J2-YK)") (class "Default")
      (node (ref "J2") (pin "10") (pinfunction "YK_10") (pintype "passive"))
      (node (ref "R19") (pin "2") (pinfunction "2_2") (pintype "passive"))
    )
    (net (code "25") (name "Net-(J3-1)") (class "Default")
      (node (ref "J3") (pin "SIG") (pinfunction "1_SIG") (pintype "passive"))
      (node (ref "S1") (pin "3") (pinfunction "RF1_3") (pintype "bidirectional"))
    )
    (net (code "26") (name "Net-(LED1-PadA)") (class "Default")
      (node (ref "LED1") (pin "A") (pinfunction "A_A") (pintype "passive"))
      (node (ref "R21") (pin "1") (pinfunction "1_1") (pintype "passive"))
    )
    (net (code "27") (name "Net-(LED2-PadA)") (class "Default")
      (node (ref "LED2") (pin "A") (pinfunction "A_A") (pintype "passive"))
      (node (ref "R22") (pin "1") (pinfunction "1_1") (pintype "passive"))
    )
    (net (code "28") (name "Net-(LED3-PadA)") (class "Default")
      (node (ref "LED3") (pin "A") (pinfunction "A_A") (pintype "passive"))
      (node (ref "R23") (pin "1") (pinfunction "1_1") (pintype "passive"))
    )
    (net (code "29") (name "Net-(LED4-PadA)") (class "Default")
      (node (ref "LED4") (pin "A") (pinfunction "A_A") (pintype "passive"))
      (node (ref "R24") (pin "2") (pinfunction "2_2") (pintype "passive"))
    )
    (net (code "30") (name "Net-(Q1-2)") (class "Default")
      (node (ref "C2") (pin "1") (pinfunction "1_1") (pintype "passive"))
      (node (ref "Q1") (pin "3") (pinfunction "2_3") (pintype "passive"))
      (node (ref "R1") (pin "2") (pinfunction "2_2") (pintype "passive"))
      (node (ref "U1") (pin "30") (pinfunction "XI_30") (pintype "input"))
    )
    (net (code "31") (name "Net-(S1-RF2)") (class "Default")
      (node (ref "C16") (pin "1") (pinfunction "1_1") (pintype "passive"))
      (node (ref "C37") (pin "2") (pinfunction "2_2") (pintype "passive"))
      (node (ref "S1") (pin "1") (pinfunction "RF2_1") (pintype "bidirectional"))
    )
    (net (code "32") (name "Net-(U1-1V2O)") (class "Default")
      (node (ref "C4") (pin "1") (pinfunction "1_1") (pintype "passive"))
      (node (ref "U1") (pin "22") (pinfunction "1V2O_22") (pintype "output"))
    )
    (net (code "33") (name "Net-(U1-EXRES1)") (class "Default")
      (node (ref "R3") (pin "2") (pinfunction "2_2") (pintype "passive"))
      (node (ref "U1") (pin "10") (pinfunction "EXRES1_10") (pintype "bidirectional"))
    )
    (net (code "34") (name "Net-(U1-RXN)") (class "Default")
      (node (ref "R11") (pin "2") (pinfunction "2_2") (pintype "passive"))
      (node (ref "U1") (pin "5") (pinfunction "RXN_5") (pintype "input"))
    )
    (net (code "35") (name "Net-(U1-RXP)") (class "Default")
      (node (ref "R12") (pin "2") (pinfunction "2_2") (pintype "passive"))
      (node (ref "U1") (pin "6") (pinfunction "RXP_6") (pintype "input"))
    )
    (net (code "36") (name "Net-(U1-TOCAP)") (class "Default")
      (node (ref "C3") (pin "1") (pinfunction "1_1") (pintype "passive"))
      (node (ref "U1") (pin "20") (pinfunction "TOCAP_20") (pintype "output"))
    )
    (net (code "37") (name "Net-(U1-TXN)") (class "Default")
      (node (ref "R9") (pin "2") (pinfunction "2_2") (pintype "passive"))
      (node (ref "U1") (pin "1") (pinfunction "TXN_1") (pintype "output"))
    )
    (net (code "38") (name "Net-(U1-TXP)") (class "Default")
      (node (ref "R10") (pin "2") (pinfunction "2_2") (pintype "passive"))
      (node (ref "U1") (pin "2") (pinfunction "TXP_2") (pintype "output"))
    )
    (net (code "39") (name "Net-(U1-XO)") (class "Default")
      (node (ref "R1") (pin "1") (pinfunction "1_1") (pintype "passive"))
      (node (ref "R2") (pin "2") (pinfunction "2_2") (pintype "passive"))
      (node (ref "U1") (pin "31") (pinfunction "XO_31") (pintype "output"))
    )
    (net (code "40") (name "Net-(U2-DCDC_SW)") (class "Default")
      (node (ref "L1") (pin "2") (pinfunction "2_2") (pintype "passive"))
      (node (ref "U2") (pin "33") (pinfunction "DCDC_SW_33") (pintype "output"))
    )
    (net (code "41") (name "Net-(U2-DCOUPL)") (class "Default")
      (node (ref "C27") (pin "1") (pinfunction "1_1") (pintype "passive"))
      (node (ref "U2") (pin "23") (pinfunction "DCOUPL_23") (pintype "passive"))
    )
    (net (code "42") (name "Net-(U2-DIO_8)") (class "Default")
      (node (ref "SV1") (pin "5") (pinfunction "5_5") (pintype "passive"))
      (node (ref "U2") (pin "14") (pinfunction "DIO_8_14") (pintype "bidirectional"))
    )
    (net (code "43") (name "Net-(U2-DIO_9)") (class "Default")
      (node (ref "SV1") (pin "4") (pinfunction "4_4") (pintype "passive"))
      (node (ref "U2") (pin "15") (pinfunction "DIO_9_15") (pintype "bidirectional"))
    )
    (net (code "44") (name "Net-(U2-DIO_10)") (class "Default")
      (node (ref "SV1") (pin "3") (pinfunction "3_3") (pintype "passive"))
      (node (ref "U2") (pin "16") (pinfunction "DIO_10_16") (pintype "bidirectional"))
    )
    (net (code "45") (name "Net-(U2-DIO_11)") (class "Default")
      (node (ref "SV1") (pin "2") (pinfunction "2_2") (pintype "passive"))
      (node (ref "U2") (pin "17") (pinfunction "DIO_11_17") (pintype "bidirectional"))
    )
    (net (code "46") (name "Net-(U2-DIO_24)") (class "Default")
      (node (ref "SV3") (pin "2") (pinfunction "2_2") (pintype "passive"))
      (node (ref "U2") (pin "37") (pinfunction "DIO_24_37") (pintype "bidirectional"))
    )
    (net (code "47") (name "Net-(U2-DIO_25)") (class "Default")
      (node (ref "SV3") (pin "3") (pinfunction "3_3") (pintype "passive"))
      (node (ref "U2") (pin "38") (pinfunction "DIO_25_38") (pintype "bidirectional"))
    )
    (net (code "48") (name "Net-(U2-DIO_26)") (class "Default")
      (node (ref "SV3") (pin "4") (pinfunction "4_4") (pintype "passive"))
      (node (ref "U2") (pin "39") (pinfunction "DIO_26_39") (pintype "bidirectional"))
    )
    (net (code "49") (name "Net-(U2-DIO_27)") (class "Default")
      (node (ref "SV3") (pin "5") (pinfunction "5_5") (pintype "passive"))
      (node (ref "U2") (pin "40") (pinfunction "DIO_27_40") (pintype "bidirectional"))
    )
    (net (code "50") (name "Net-(U7-BIAS)") (class "Default")
      (node (ref "C33") (pin "1") (pinfunction "1_1") (pintype "passive"))
      (node (ref "U7") (pin "5") (pinfunction "BIAS_5") (pintype "passive"))
    )
    (net (code "51") (name "Net-(X1-PadS1)") (class "Default")
      (node (ref "X1") (pin "S1") (pinfunction "S1_S1") (pintype "passive"))
      (node (ref "X1") (pin "S2") (pinfunction "S2_S2") (pintype "passive"))
      (node (ref "X1") (pin "S3") (pinfunction "S3_S3") (pintype "passive"))
      (node (ref "X1") (pin "S4") (pinfunction "S4_S4") (pintype "passive"))
    )
    (net (code "52") (name "POWER_OK") (class "Default")
      (node (ref "U7") (pin "2") (pinfunction "POK_2") (pintype "output"))
    )
    (net (code "53") (name "RF_N") (class "Default")
      (node (ref "FL2") (pin "3") (pinfunction "BALP2_3") (pintype "passive"))
      (node (ref "U2") (pin "2") (pinfunction "RF_N_2") (pintype "bidirectional"))
    )
    (net (code "54") (name "RF_P") (class "Default")
      (node (ref "FL2") (pin "4") (pinfunction "BALP3_4") (pintype "passive"))
      (node (ref "U2") (pin "1") (pinfunction "RF_P_1") (pintype "bidirectional"))
    )
    (net (code "55") (name "RTS") (class "Default")
      (node (ref "IC1") (pin "24") (pinfunction "RTS_24") (pintype "output"))
    )
    (net (code "56") (name "RXD") (class "Default")
      (node (ref "IC1") (pin "26") (pinfunction "TXD_26") (pintype "output"))
      (node (ref "R5") (pin "2") (pinfunction "2_2") (pintype "passive"))
    )
    (net (code "57") (name "SEL") (class "Default")
      (node (ref "R7") (pin "1") (pinfunction "1_1") (pintype "passive"))
      (node (ref "U7") (pin "1") (pinfunction "SEL_1") (pintype "passive"))
    )
    (net (code "58") (name "TCK") (class "Default")
      (node (ref "SV2") (pin "4") (pinfunction "4_4") (pintype "passive"))
      (node (ref "U2") (pin "25") (pinfunction "JTAG_TCKC_25") (pintype "input"))
    )
    (net (code "59") (name "TDI") (class "Default")
      (node (ref "SV2") (pin "8") (pinfunction "8_8") (pintype "passive"))
      (node (ref "U2") (pin "27") (pinfunction "DIO_17_27") (pintype "bidirectional"))
    )
    (net (code "60") (name "TDO") (class "Default")
      (node (ref "SV2") (pin "6") (pinfunction "6_6") (pintype "passive"))
      (node (ref "U2") (pin "26") (pinfunction "DIO_16_26") (pintype "bidirectional"))
    )
    (net (code "61") (name "TMS") (class "Default")
      (node (ref "SV2") (pin "2") (pinfunction "2_2") (pintype "passive"))
      (node (ref "U2") (pin "24") (pinfunction "JTAG_TMSC_24") (pintype "bidirectional"))
    )
    (net (code "62") (name "TXD") (class "Default")
      (node (ref "IC1") (pin "25") (pinfunction "RXD_25") (pintype "input"))
      (node (ref "R6") (pin "2") (pinfunction "2_2") (pintype "passive"))
    )
    (net (code "63") (name "USB_N") (class "Default")
      (node (ref "IC1") (pin "5") (pinfunction "D-_5") (pintype "bidirectional"))
      (node (ref "X1") (pin "2") (pinfunction "2_2") (pintype "input"))
    )
    (net (code "64") (name "USB_P") (class "Default")
      (node (ref "IC1") (pin "4") (pinfunction "D+_4") (pintype "bidirectional"))
      (node (ref "X1") (pin "3") (pinfunction "3_3") (pintype "input"))
    )
    (net (code "65") (name "VCC5") (class "Default")
      (node (ref "C35") (pin "1") (pinfunction "1_1") (pintype "passive"))
      (node (ref "R8") (pin "2") (pinfunction "2_2") (pintype "passive"))
      (node (ref "U7") (pin "3") (pinfunction "EN_3") (pintype "input"))
      (node (ref "U7") (pin "6") (pinfunction "IN_6") (pintype "input"))
      (node (ref "X1") (pin "1") (pinfunction "1_1") (pintype "input"))
    )
    (net (code "66") (name "VUSB") (class "Default")
      (node (ref "C29") (pin "1") (pinfunction "1_1") (pintype "passive"))
      (node (ref "IC1") (pin "7") (pinfunction "REGIN_7") (pintype "passive"))
      (node (ref "IC1") (pin "8") (pinfunction "VBUS_8") (pintype "input"))
      (node (ref "R8") (pin "1") (pinfunction "1_1") (pintype "passive"))
    )
    (net (code "67") (name "W_ACTLED") (class "Default")
      (node (ref "R18") (pin "1") (pinfunction "1_1") (pintype "passive"))
      (node (ref "U1") (pin "27") (pinfunction "ACTLED_27") (pintype "output"))
    )
    (net (code "68") (name "W_CLK") (class "Default")
      (node (ref "U1") (pin "33") (pinfunction "SCLK_33") (pintype "input"))
      (node (ref "U2") (pin "31") (pinfunction "DIO_21_31") (pintype "bidirectional"))
    )
    (net (code "69") (name "W_CS") (class "Default")
      (node (ref "U1") (pin "32") (pinfunction "~{SCSN}_32") (pintype "input"))
      (node (ref "U2") (pin "32") (pinfunction "DIO_22_32") (pintype "bidirectional"))
    )
    (net (code "70") (name "W_INT") (class "Default")
      (node (ref "U1") (pin "36") (pinfunction "~{INTN}_36") (pintype "input"))
      (node (ref "U2") (pin "28") (pinfunction "DIO_18_28") (pintype "bidirectional"))
    )
    (net (code "71") (name "W_LINKLED") (class "Default")
      (node (ref "R19") (pin "1") (pinfunction "1_1") (pintype "passive"))
      (node (ref "U1") (pin "25") (pinfunction "LINKLED_25") (pintype "output"))
    )
    (net (code "72") (name "W_MISO") (class "Default")
      (node (ref "U1") (pin "34") (pinfunction "MISO_34") (pintype "output"))
      (node (ref "U2") (pin "30") (pinfunction "DIO_20_30") (pintype "bidirectional"))
    )
    (net (code "73") (name "W_MOSI") (class "Default")
      (node (ref "U1") (pin "35") (pinfunction "MOSI_35") (pintype "input"))
      (node (ref "U2") (pin "29") (pinfunction "DIO_19_29") (pintype "bidirectional"))
    )
    (net (code "74") (name "W_RX_N") (class "Default")
      (node (ref "C17") (pin "1") (pinfunction "1_1") (pintype "passive"))
      (node (ref "R11") (pin "1") (pinfunction "1_1") (pintype "passive"))
      (node (ref "R16") (pin "2") (pinfunction "2_2") (pintype "passive"))
    )
    (net (code "75") (name "W_RX_P") (class "Default")
      (node (ref "C13") (pin "1") (pinfunction "1_1") (pintype "passive"))
      (node (ref "R12") (pin "1") (pinfunction "1_1") (pintype "passive"))
      (node (ref "R17") (pin "2") (pinfunction "2_2") (pintype "passive"))
    )
    (net (code "76") (name "W_TX_N") (class "Default")
      (node (ref "J2") (pin "3") (pinfunction "TD-_3") (pintype "passive"))
      (node (ref "R13") (pin "1") (pinfunction "1_1") (pintype "passive"))
      (node (ref "R9") (pin "1") (pinfunction "1_1") (pintype "passive"))
    )
    (net (code "77") (name "W_TX_P") (class "Default")
      (node (ref "J2") (pin "1") (pinfunction "TD+_1") (pintype "passive"))
      (node (ref "R10") (pin "1") (pinfunction "1_1") (pintype "passive"))
      (node (ref "R14") (pin "1") (pinfunction "1_1") (pintype "passive"))
    )
    (net (code "78") (name "unconnected-(IC1-CTS-Pad23)") (class "Default")
      (node (ref "IC1") (pin "23") (pinfunction "CTS_23") (pintype "input"))
    )
    (net (code "79") (name "unconnected-(IC1-DCD-Pad1)") (class "Default")
      (node (ref "IC1") (pin "1") (pinfunction "DCD_1") (pintype "input"))
    )
    (net (code "80") (name "unconnected-(IC1-DSR-Pad27)") (class "Default")
      (node (ref "IC1") (pin "27") (pinfunction "DSR_27") (pintype "input"))
    )
    (net (code "81") (name "unconnected-(IC1-RI-Pad2)") (class "Default")
      (node (ref "IC1") (pin "2") (pinfunction "RI_2") (pintype "input"))
    )
    (net (code "82") (name "unconnected-(IC1-SUSPEND-Pad12)") (class "Default")
      (node (ref "IC1") (pin "12") (pinfunction "SUSPEND_12") (pintype "output"))
    )
    (net (code "83") (name "unconnected-(IC1-~{RST}-Pad9)") (class "Default")
      (node (ref "IC1") (pin "9") (pinfunction "~{RST}_9") (pintype "bidirectional"))
    )
    (net (code "84") (name "unconnected-(IC1-~{SUSPEND}-Pad11)") (class "Default")
      (node (ref "IC1") (pin "11") (pinfunction "~{SUSPEND}_11") (pintype "output"))
    )
    (net (code "85") (name "unconnected-(J2-P8-Pad8)") (class "Default")
      (node (ref "J2") (pin "8") (pinfunction "P8_8") (pintype "passive"))
    )
    (net (code "86") (name "unconnected-(JP4-Pad1)") (class "Default")
      (node (ref "JP4") (pin "1") (pinfunction "1_1") (pintype "passive"))
    )
    (net (code "87") (name "unconnected-(SV2-Pad7)") (class "Default")
      (node (ref "SV2") (pin "7") (pinfunction "7_7") (pintype "passive"))
    )
    (net (code "88") (name "unconnected-(U1-DNC-Pad7)") (class "Default")
      (node (ref "U1") (pin "7") (pinfunction "DNC_7") (pintype "bidirectional"))
    )
    (net (code "89") (name "unconnected-(U1-DUPLED-Pad26)") (class "Default")
      (node (ref "U1") (pin "26") (pinfunction "DUPLED_26") (pintype "output"))
    )
    (net (code "90") (name "unconnected-(U1-RSVD1-Pad23)") (class "Default")
      (node (ref "U1") (pin "23") (pinfunction "RSVD1_23") (pintype "input"))
    )
    (net (code "91") (name "unconnected-(U1-RSVD2-Pad38)") (class "Default")
      (node (ref "U1") (pin "38") (pinfunction "RSVD2_38") (pintype "input"))
    )
    (net (code "92") (name "unconnected-(U1-RSVD3-Pad39)") (class "Default")
      (node (ref "U1") (pin "39") (pinfunction "RSVD3_39") (pintype "input"))
    )
    (net (code "93") (name "unconnected-(U1-RSVD4-Pad40)") (class "Default")
      (node (ref "U1") (pin "40") (pinfunction "RSVD4_40") (pintype "input"))
    )
    (net (code "94") (name "unconnected-(U1-RSVD5-Pad41)") (class "Default")
      (node (ref "U1") (pin "41") (pinfunction "RSVD5_41") (pintype "input"))
    )
    (net (code "95") (name "unconnected-(U1-RSVD6-Pad42)") (class "Default")
      (node (ref "U1") (pin "42") (pinfunction "RSVD6_42") (pintype "input"))
    )
    (net (code "96") (name "unconnected-(U1-SPDLED-Pad24)") (class "Default")
      (node (ref "U1") (pin "24") (pinfunction "SPDLED_24") (pintype "output"))
    )
    (net (code "97") (name "unconnected-(U1-VBG-Pad18)") (class "Default")
      (node (ref "U1") (pin "18") (pinfunction "VBG_18") (pintype "output"))
    )
    (net (code "98") (name "unconnected-(U1-~{RSTN}-Pad37)") (class "Default")
      (node (ref "U1") (pin "37") (pinfunction "~{RSTN}_37") (pintype "input"))
    )
    (net (code "99") (name "unconnected-(U2-DIO_1-Pad6)") (class "Default")
      (node (ref "U2") (pin "6") (pinfunction "DIO_1_6") (pintype "bidirectional"))
    )
    (net (code "100") (name "unconnected-(U2-DIO_2-Pad7)") (class "Default")
      (node (ref "U2") (pin "7") (pinfunction "DIO_2_7") (pintype "bidirectional"))
    )
    (net (code "101") (name "unconnected-(U2-DIO_3-Pad8)") (class "Default")
      (node (ref "U2") (pin "8") (pinfunction "DIO_3_8") (pintype "bidirectional"))
    )
    (net (code "102") (name "unconnected-(U2-DIO_4-Pad9)") (class "Default")
      (node (ref "U2") (pin "9") (pinfunction "DIO_4_9") (pintype "bidirectional"))
    )
    (net (code "103") (name "unconnected-(U2-DIO_12-Pad18)") (class "Default")
      (node (ref "U2") (pin "18") (pinfunction "DIO_12_18") (pintype "bidirectional"))
    )
    (net (code "104") (name "unconnected-(U2-DIO_13-Pad19)") (class "Default")
      (node (ref "U2") (pin "19") (pinfunction "DIO_13_19") (pintype "bidirectional"))
    )
    (net (code "105") (name "unconnected-(U2-DIO_23-Pad36)") (class "Default")
      (node (ref "U2") (pin "36") (pinfunction "DIO_23_36") (pintype "bidirectional"))
    )
    (net (code "106") (name "unconnected-(U2-DIO_28-Pad41)") (class "Default")
      (node (ref "U2") (pin "41") (pinfunction "DIO_28_41") (pintype "bidirectional"))
    )
    (net (code "107") (name "unconnected-(U2-DIO_29-Pad42)") (class "Default")
      (node (ref "U2") (pin "42") (pinfunction "DIO_29_42") (pintype "bidirectional"))
    )
    (net (code "108") (name "unconnected-(U2-DIO_30-Pad43)") (class "Default")
      (node (ref "U2") (pin "43") (pinfunction "DIO_30_43") (pintype "bidirectional"))
    )
    (net (code "109") (name "unconnected-(U2-X32K_Q1-Pad3)") (class "Default")
      (node (ref "U2") (pin "3") (pinfunction "X32K_Q1_3") (pintype "bidirectional"))
    )
    (net (code "110") (name "unconnected-(U2-X32K_Q2-Pad4)") (class "Default")
      (node (ref "U2") (pin "4") (pinfunction "X32K_Q2_4") (pintype "bidirectional"))
    )
    (net (code "111") (name "unconnected-(U2-X48M_N-Pad46)") (class "Default")
      (node (ref "U2") (pin "46") (pinfunction "X48M_N_46") (pintype "bidirectional"))
    )
    (net (code "112") (name "unconnected-(U2-X48M_P-Pad47)") (class "Default")
      (node (ref "U2") (pin "47") (pinfunction "X48M_P_47") (pintype "bidirectional"))
    )
    (net (code "113") (name "unconnected-(X1-Pad4)") (class "Default")
      (node (ref "X1") (pin "4") (pinfunction "4_4") (pintype "input"))
    )
  )
)
